# dash_power_supply.net
KiCad netlist of a schematic drawn in EAGLE
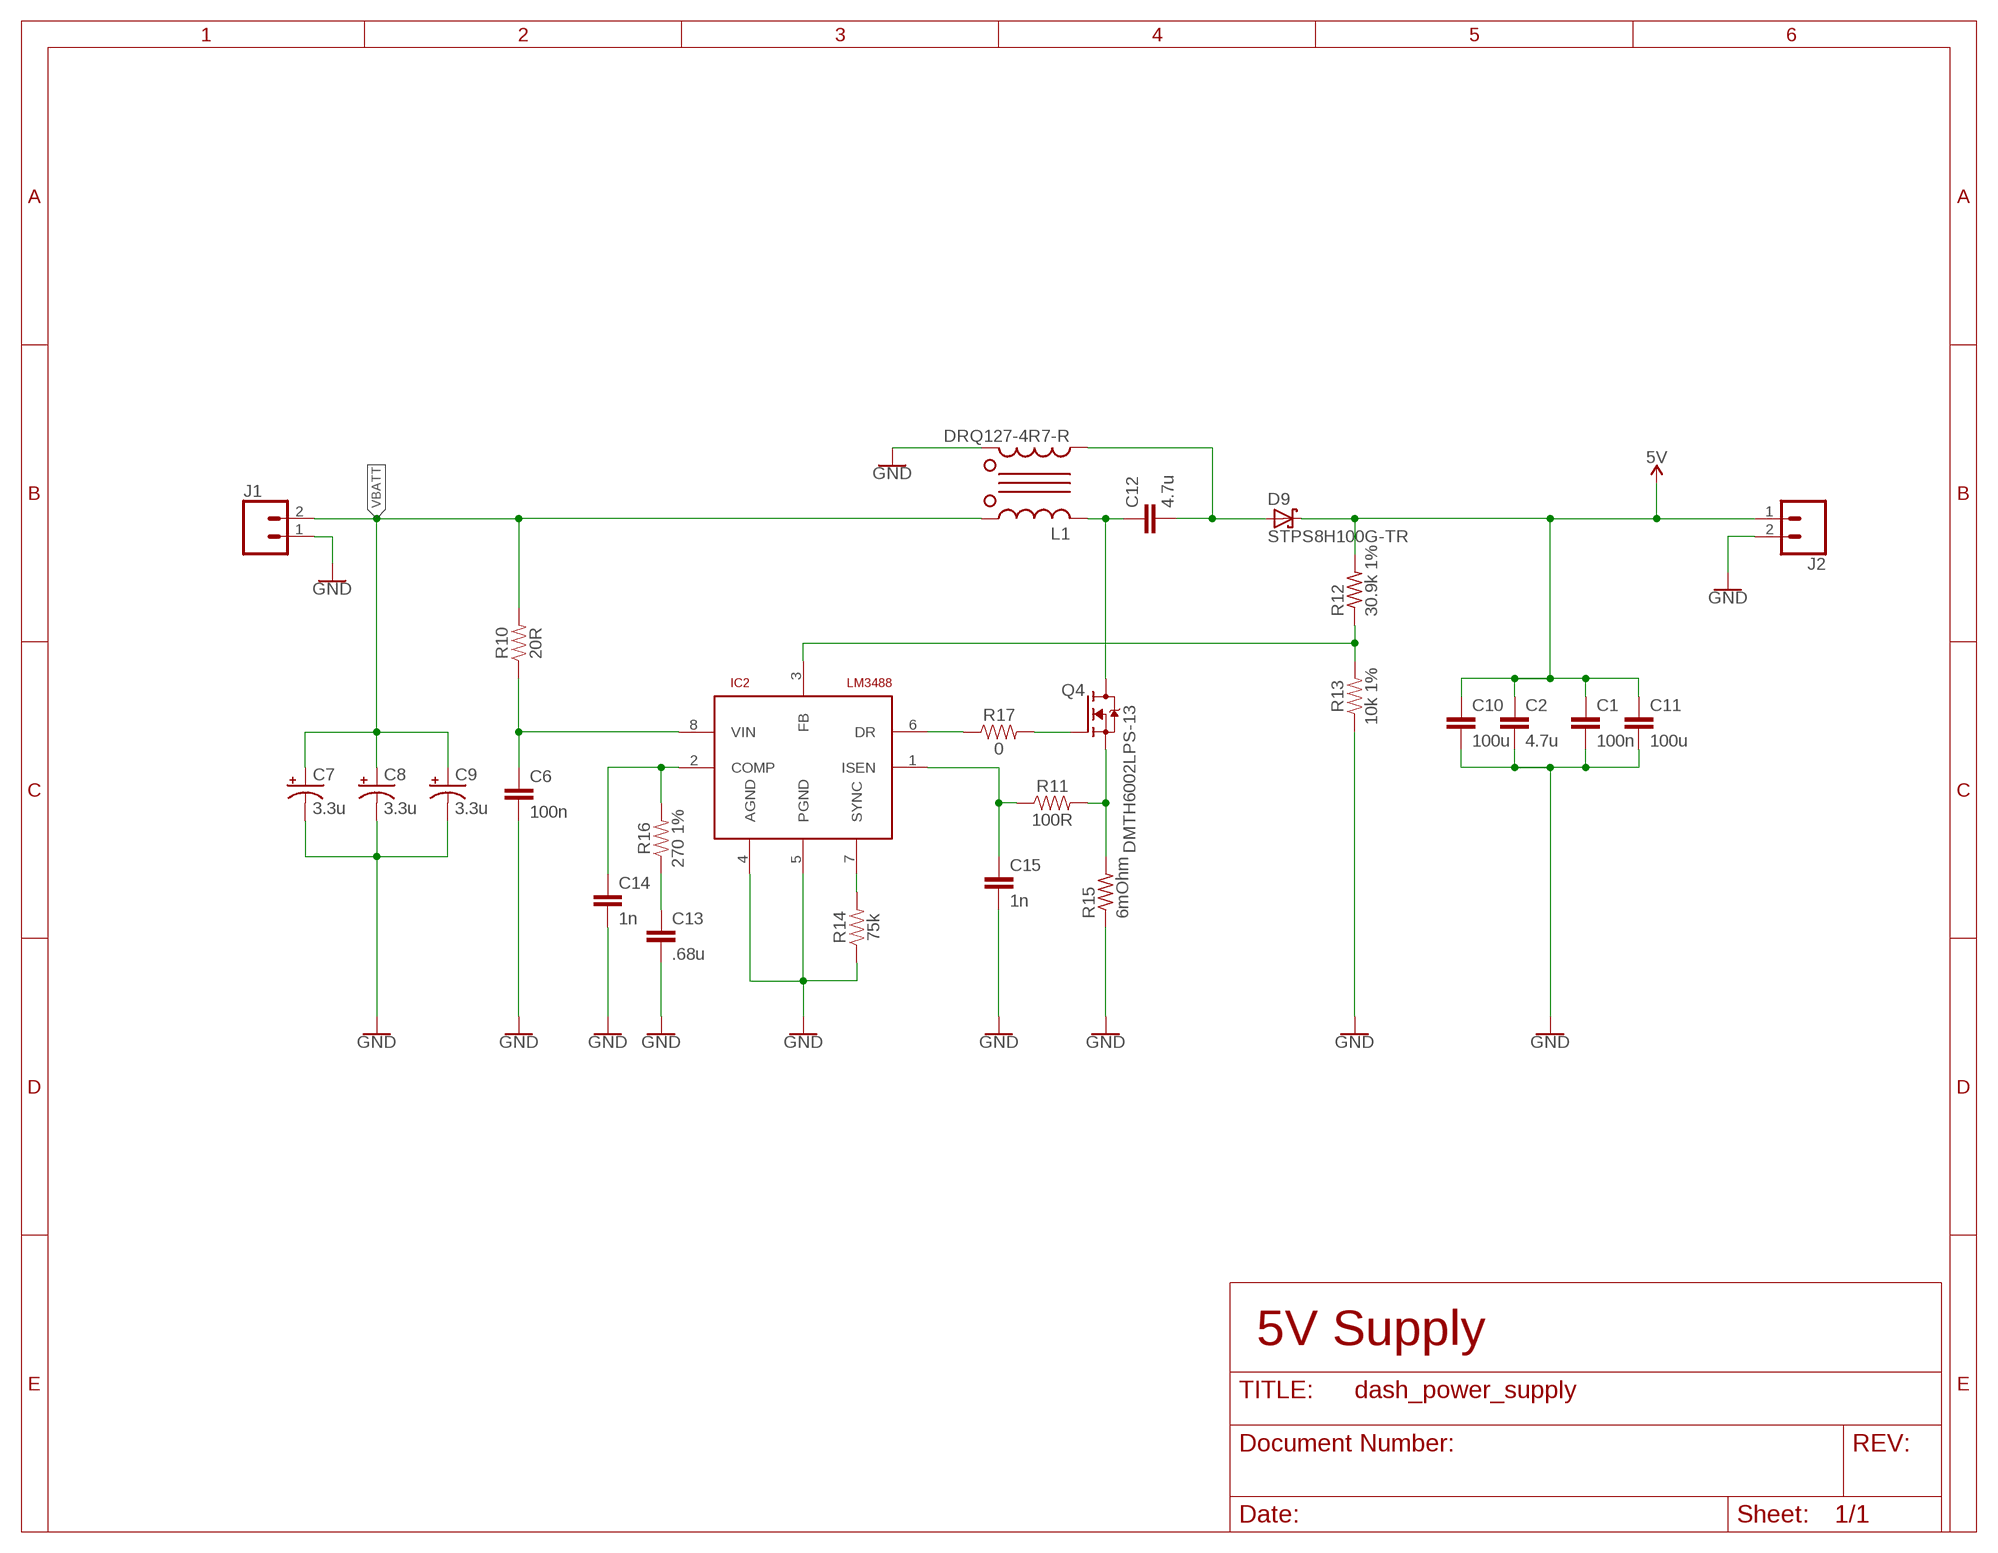
[diagram p0: schematic, sheet 1]

(export (version "E")
  (design (tool "Eeschema 10.0.6"))
  (components
    (comp (ref "C1")
      (value "100n")
      (footprint "eagle-import:0603")
      (fields (field (name "VOLTAGE") "50V"))
      (libsource (lib "eagle-import") (part "CL10B104MB8NNNC"))
    )
    (comp (ref "C2")
      (value "4.7u")
      (footprint "eagle-import:0603")
      (fields (field (name "VOLTAGE") "35V"))
      (libsource (lib "eagle-import") (part "CL10A475KL8NRNC"))
    )
    (comp (ref "C6")
      (value "100n")
      (footprint "eagle-import:0603")
      (fields (field (name "VOLTAGE") "50V"))
      (libsource (lib "eagle-import") (part "CL10B104MB8NNNC"))
    )
    (comp (ref "C7")
      (value "3.3u")
      (footprint "eagle-import:PANASONIC_C")
      (fields (field (name "VOLTAGE") "80v"))
      (libsource (lib "eagle-import") (part "EEV-FK1K3R3R"))
    )
    (comp (ref "C8")
      (value "3.3u")
      (footprint "eagle-import:PANASONIC_C")
      (fields (field (name "VOLTAGE") "80v"))
      (libsource (lib "eagle-import") (part "EEV-FK1K3R3R"))
    )
    (comp (ref "C9")
      (value "3.3u")
      (footprint "eagle-import:PANASONIC_C")
      (fields (field (name "VOLTAGE") "80v"))
      (libsource (lib "eagle-import") (part "EEV-FK1K3R3R"))
    )
    (comp (ref "C10")
      (value "100u")
      (footprint "eagle-import:C1210")
      (fields (field (name "VOLTAGE") "10V"))
      (libsource (lib "eagle-import") (part "CL32A107MPVNNNE"))
    )
    (comp (ref "C11")
      (value "100u")
      (footprint "eagle-import:C1210")
      (fields (field (name "VOLTAGE") "10V"))
      (libsource (lib "eagle-import") (part "CL32A107MPVNNNE"))
    )
    (comp (ref "C12")
      (value "4.7u")
      (footprint "eagle-import:0603")
      (fields (field (name "VOLTAGE") "35V"))
      (libsource (lib "eagle-import") (part "CL10A475KL8NRNC"))
    )
    (comp (ref "C13")
      (value ".68u")
      (footprint "eagle-import:0603")
      (fields (field (name "VOLTAGE") "16V"))
      (libsource (lib "eagle-import") (part "CL10B684KO8NFNC"))
    )
    (comp (ref "C14")
      (value "1n")
      (footprint "eagle-import:0603")
      (fields (field (name "VOLTAGE") "50V"))
      (libsource (lib "eagle-import") (part "CL10B102KB8NNWC"))
    )
    (comp (ref "C15")
      (value "1n")
      (footprint "eagle-import:0603")
      (fields (field (name "VOLTAGE") "50V"))
      (libsource (lib "eagle-import") (part "CL10B102KB8NNWC"))
    )
    (comp (ref "D9")
      (value "STPS8H100G-TR")
      (footprint "eagle-import:TO263")
      (libsource (lib "eagle-import") (part "STPS8H100G-TR"))
    )
    (comp (ref "IC2")
      (value "LM3488")
      (footprint "eagle-import:VSSOP-8")
      (libsource (lib "eagle-import") (part "LM3488"))
    )
    (comp (ref "J1")
      (value "CONN_02PTH4")
      (footprint "eagle-import:1X02_XTRA_BIG")
      (libsource (lib "eagle-import") (part "CONN_02PTH4"))
    )
    (comp (ref "J2")
      (value "CONN_02PTH4")
      (footprint "eagle-import:1X02_XTRA_BIG")
      (libsource (lib "eagle-import") (part "CONN_02PTH4"))
    )
    (comp (ref "L1")
      (value "DRQ127-4R7-R")
      (footprint "eagle-import:DRQ127")
      (libsource (lib "eagle-import") (part "DRQ127-4R7-R"))
    )
    (comp (ref "Q4")
      (value "DMTH6002LPS-13")
      (footprint "eagle-import:TDSON")
      (libsource (lib "eagle-import") (part "DMTH6002LPS-13"))
    )
    (comp (ref "R10")
      (value "20R")
      (footprint "eagle-import:0603")
      (libsource (lib "eagle-import") (part "RC0603JR-0720RL"))
    )
    (comp (ref "R11")
      (value "100R")
      (footprint "eagle-import:0603")
      (libsource (lib "eagle-import") (part "RC0603JR-07100RL"))
    )
    (comp (ref "R12")
      (value "30.9k 1%")
      (footprint "eagle-import:R1206")
      (fields (field (name "POWER") ".25W"))
      (libsource (lib "eagle-import") (part "RC1206FR-0730K9L"))
    )
    (comp (ref "R13")
      (value "10k 1%")
      (footprint "eagle-import:0603")
      (libsource (lib "eagle-import") (part "RC0603FR-1010KL"))
    )
    (comp (ref "R14")
      (value "75k")
      (footprint "eagle-import:0603")
      (libsource (lib "eagle-import") (part "75KOHM-0603-1/10W-1%"))
    )
    (comp (ref "R15")
      (value "6mOhm")
      (footprint "eagle-import:3216")
      (fields (field (name "POWER") "1W"))
      (libsource (lib "eagle-import") (part "PRL1632-R006-F-T1"))
    )
    (comp (ref "R16")
      (value "270 1%")
      (footprint "eagle-import:0603")
      (libsource (lib "eagle-import") (part "RC0603FR-07270RL"))
    )
    (comp (ref "R17")
      (value "0")
      (footprint "eagle-import:0603")
      (libsource (lib "eagle-import") (part "0OHM-0603-1/10W"))
    )
  )
  (nets
    (net (code "1") (name "5V") (class "Default")
      (node (ref "C1") (pin "1") (pinfunction "1_1") (pintype "passive"))
      (node (ref "C10") (pin "1") (pinfunction "1_1") (pintype "passive"))
      (node (ref "C11") (pin "1") (pinfunction "1_1") (pintype "passive"))
      (node (ref "C2") (pin "1") (pinfunction "1_1") (pintype "passive"))
      (node (ref "D9") (pin "3") (pinfunction "C_3") (pintype "passive"))
      (node (ref "J2") (pin "1") (pinfunction "1_1") (pintype "passive"))
      (node (ref "R12") (pin "2") (pinfunction "2_2") (pintype "passive"))
    )
    (net (code "2") (name "GND") (class "Default")
      (node (ref "C1") (pin "2") (pinfunction "2_2") (pintype "passive"))
      (node (ref "C10") (pin "2") (pinfunction "2_2") (pintype "passive"))
      (node (ref "C11") (pin "2") (pinfunction "2_2") (pintype "passive"))
      (node (ref "C13") (pin "2") (pinfunction "2_2") (pintype "passive"))
      (node (ref "C14") (pin "2") (pinfunction "2_2") (pintype "passive"))
      (node (ref "C15") (pin "2") (pinfunction "2_2") (pintype "passive"))
      (node (ref "C2") (pin "2") (pinfunction "2_2") (pintype "passive"))
      (node (ref "C6") (pin "2") (pinfunction "2_2") (pintype "passive"))
      (node (ref "C7") (pin "-") (pinfunction "-_-") (pintype "passive"))
      (node (ref "C8") (pin "-") (pinfunction "-_-") (pintype "passive"))
      (node (ref "C9") (pin "-") (pinfunction "-_-") (pintype "passive"))
      (node (ref "IC2") (pin "4") (pinfunction "AGND_4") (pintype "bidirectional"))
      (node (ref "IC2") (pin "5") (pinfunction "PGND_5") (pintype "bidirectional"))
      (node (ref "J1") (pin "1") (pinfunction "1_1") (pintype "passive"))
      (node (ref "J2") (pin "2") (pinfunction "2_2") (pintype "passive"))
      (node (ref "L1") (pin "2") (pinfunction "2_2") (pintype "passive"))
      (node (ref "R13") (pin "1") (pinfunction "1_1") (pintype "passive"))
      (node (ref "R14") (pin "1") (pinfunction "1_1") (pintype "passive"))
      (node (ref "R15") (pin "1") (pinfunction "1_1") (pintype "passive"))
    )
    (net (code "3") (name "Net-(C13-Pad1)") (class "Default")
      (node (ref "C13") (pin "1") (pinfunction "1_1") (pintype "passive"))
      (node (ref "R16") (pin "1") (pinfunction "1_1") (pintype "passive"))
    )
    (net (code "4") (name "Net-(D9-A)") (class "Default")
      (node (ref "C12") (pin "2") (pinfunction "2_2") (pintype "passive"))
      (node (ref "D9") (pin "2") (pinfunction "A_2") (pintype "passive"))
      (node (ref "L1") (pin "4") (pinfunction "4_4") (pintype "passive"))
    )
    (net (code "5") (name "Net-(IC2-COMP)") (class "Default")
      (node (ref "C14") (pin "1") (pinfunction "1_1") (pintype "passive"))
      (node (ref "IC2") (pin "2") (pinfunction "COMP_2") (pintype "bidirectional"))
      (node (ref "R16") (pin "2") (pinfunction "2_2") (pintype "passive"))
    )
    (net (code "6") (name "Net-(IC2-DR)") (class "Default")
      (node (ref "IC2") (pin "6") (pinfunction "DR_6") (pintype "bidirectional"))
      (node (ref "R17") (pin "1") (pinfunction "1_1") (pintype "passive"))
    )
    (net (code "7") (name "Net-(IC2-FB)") (class "Default")
      (node (ref "IC2") (pin "3") (pinfunction "FB_3") (pintype "bidirectional"))
      (node (ref "R12") (pin "1") (pinfunction "1_1") (pintype "passive"))
      (node (ref "R13") (pin "2") (pinfunction "2_2") (pintype "passive"))
    )
    (net (code "8") (name "Net-(IC2-ISEN)") (class "Default")
      (node (ref "C15") (pin "1") (pinfunction "1_1") (pintype "passive"))
      (node (ref "IC2") (pin "1") (pinfunction "ISEN_1") (pintype "bidirectional"))
      (node (ref "R11") (pin "1") (pinfunction "1_1") (pintype "passive"))
    )
    (net (code "9") (name "Net-(IC2-SYNC)") (class "Default")
      (node (ref "IC2") (pin "7") (pinfunction "SYNC_7") (pintype "bidirectional"))
      (node (ref "R14") (pin "2") (pinfunction "2_2") (pintype "passive"))
    )
    (net (code "10") (name "Net-(IC2-VIN)") (class "Default")
      (node (ref "C6") (pin "1") (pinfunction "1_1") (pintype "passive"))
      (node (ref "IC2") (pin "8") (pinfunction "VIN_8") (pintype "bidirectional"))
      (node (ref "R10") (pin "1") (pinfunction "1_1") (pintype "passive"))
    )
    (net (code "11") (name "Net-(Q4-D)") (class "Default")
      (node (ref "C12") (pin "1") (pinfunction "1_1") (pintype "passive"))
      (node (ref "L1") (pin "3") (pinfunction "3_3") (pintype "passive"))
      (node (ref "Q4") (pin "5") (pinfunction "D_5") (pintype "passive"))
    )
    (net (code "12") (name "Net-(Q4-G)") (class "Default")
      (node (ref "Q4") (pin "4") (pinfunction "G_4") (pintype "passive"))
      (node (ref "R17") (pin "2") (pinfunction "2_2") (pintype "passive"))
    )
    (net (code "13") (name "Net-(Q4-S-Pad1)") (class "Default")
      (node (ref "Q4") (pin "1") (pinfunction "S_1") (pintype "passive"))
      (node (ref "Q4") (pin "2") (pinfunction "S_2") (pintype "passive"))
      (node (ref "Q4") (pin "3") (pinfunction "S_3") (pintype "passive"))
      (node (ref "R11") (pin "2") (pinfunction "2_2") (pintype "passive"))
      (node (ref "R15") (pin "2") (pinfunction "2_2") (pintype "passive"))
    )
    (net (code "14") (name "VBATT") (class "Default")
      (node (ref "C7") (pin "+") (pinfunction "+_+") (pintype "passive"))
      (node (ref "C8") (pin "+") (pinfunction "+_+") (pintype "passive"))
      (node (ref "C9") (pin "+") (pinfunction "+_+") (pintype "passive"))
      (node (ref "J1") (pin "2") (pinfunction "2_2") (pintype "passive"))
      (node (ref "L1") (pin "1") (pinfunction "1_1") (pintype "passive"))
      (node (ref "R10") (pin "2") (pinfunction "2_2") (pintype "passive"))
    )
  )
)
